# SC2.net
KiCad netlist of a schematic drawn in Altium Designer
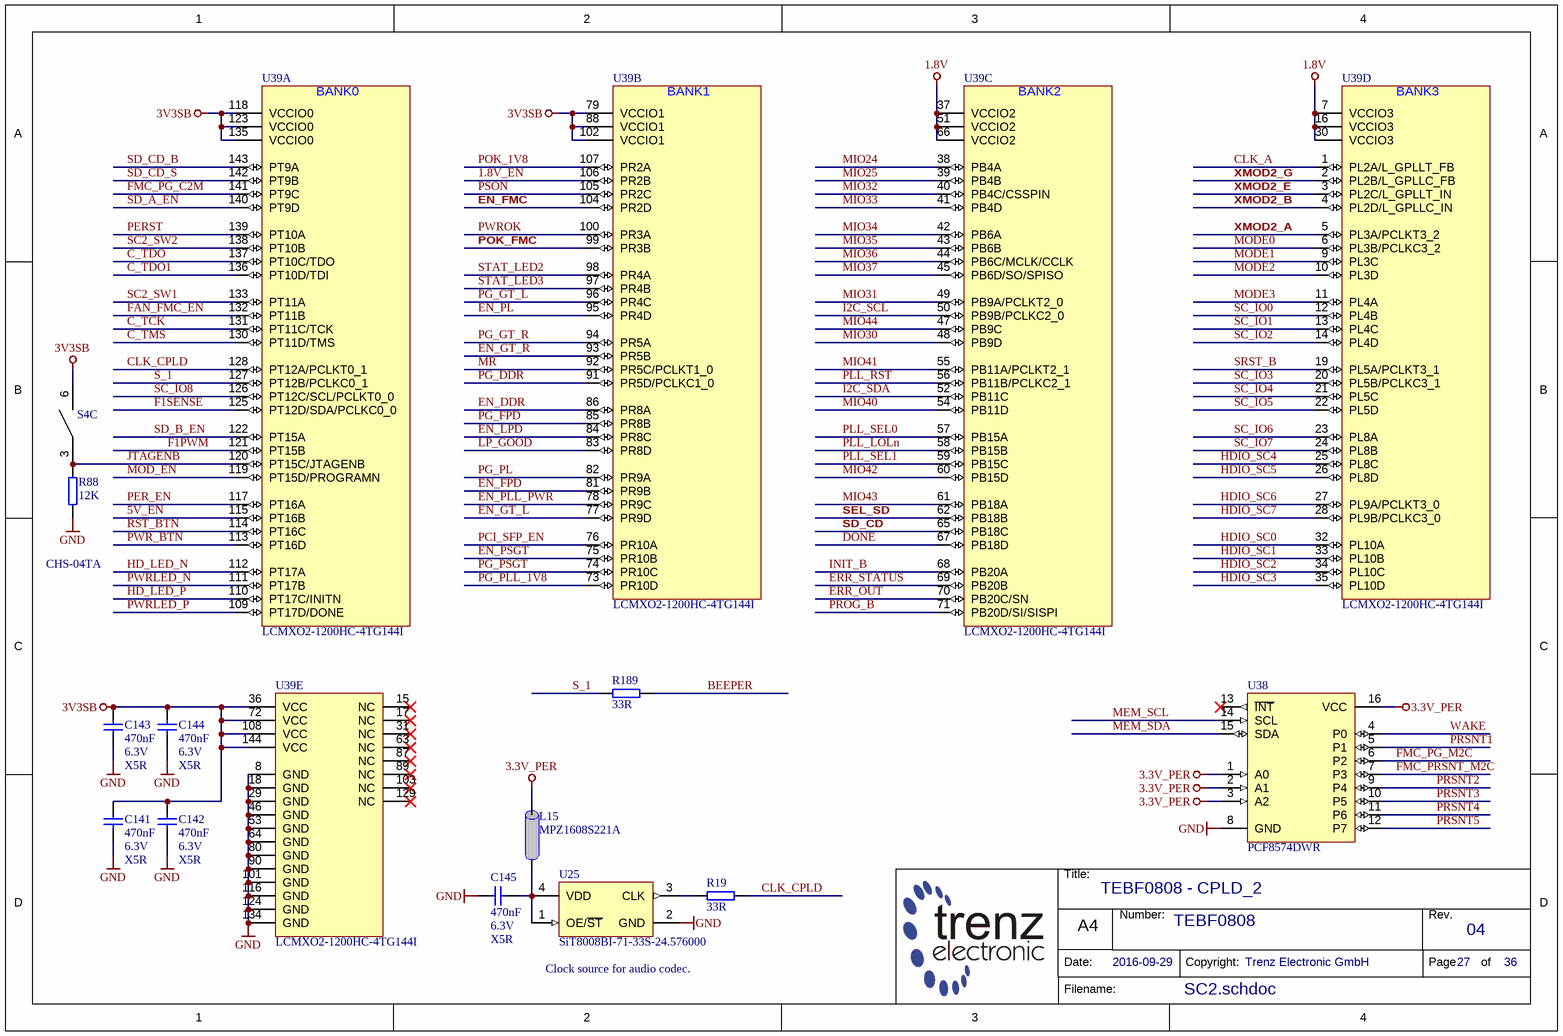
[diagram p0: SC2.schdoc]

(export (version "E")
  (design (tool "Eeschema 10.0.6"))
  (components
    (comp (ref "C141")
      (value "470nF")
      (footprint "CAPC1005X55N")
      (description "KON 470nF 6,3V X5R SMD")
      (fields (field (name "VOLTAGE") "6.3V") (field (name "TECHNOLOGY") "X5R"))
      (libsource (lib "TE") (part "CAP-NP"))
    )
    (comp (ref "C142")
      (value "470nF")
      (footprint "CAPC1005X55N")
      (description "KON 470nF 6,3V X5R SMD")
      (fields (field (name "VOLTAGE") "6.3V") (field (name "TECHNOLOGY") "X5R"))
      (libsource (lib "TE") (part "CAP-NP"))
    )
    (comp (ref "C143")
      (value "470nF")
      (footprint "CAPC1005X55N")
      (description "KON 470nF 6,3V X5R SMD")
      (fields (field (name "VOLTAGE") "6.3V") (field (name "TECHNOLOGY") "X5R"))
      (libsource (lib "TE") (part "CAP-NP"))
    )
    (comp (ref "C144")
      (value "470nF")
      (footprint "CAPC1005X55N")
      (description "KON 470nF 6,3V X5R SMD")
      (fields (field (name "VOLTAGE") "6.3V") (field (name "TECHNOLOGY") "X5R"))
      (libsource (lib "TE") (part "CAP-NP"))
    )
    (comp (ref "C145")
      (value "470nF")
      (footprint "CAPC1005X55N")
      (description "KON 470nF 6,3V X5R SMD")
      (fields (field (name "VOLTAGE") "6.3V") (field (name "TECHNOLOGY") "X5R"))
      (libsource (lib "TE") (part "CAP-NP"))
    )
    (comp (ref "L15")
      (value "MPZ1608S221A")
      (footprint "INDC1608X95N")
      (description "Ferritdurchführung MPZ1608S221A")
      (libsource (lib "TE") (part "Ferritperle"))
    )
    (comp (ref "R19")
      (value "33R")
      (footprint "RESC1005X40N")
      (description "WID SMD 33R 1% 0,063W")
      (fields (field (name "TOLERANCE") "1%"))
      (libsource (lib "TE") (part "RES"))
    )
    (comp (ref "R88")
      (value "12K")
      (footprint "RESC1005X40N")
      (description "WID SMD 12K 1% 0,063W")
      (fields (field (name "TOLERANCE") "1%"))
      (libsource (lib "TE") (part "RES"))
    )
    (comp (ref "R189")
      (value "33R")
      (footprint "RESC1005X40N")
      (description "WID SMD 33R 1% 0,063W")
      (fields (field (name "TOLERANCE") "1%"))
      (libsource (lib "TE") (part "RES"))
    )
    (comp (ref "S4")
      (value "CHS-04TA")
      (footprint "CHS-04TA")
      (description "DIP Schalter 4 fach 1,27mm SMD")
      (libsource (lib "TE") (part "CHS-04TA"))
    )
    (comp (ref "U25")
      (value "SiT8008BI-71-33S-24.576000")
      (footprint "2016")
      (description "SiT8008BI-71-33S-24.576000 MEMS Oszillator 24.576000MHz")
      (libsource (lib "TE") (part "SiT8103"))
    )
    (comp (ref "U38")
      (value "PCF8574DWR")
      (footprint "SOIC127P1030X265-16N")
      (libsource (lib "TE") (part "PCF8574DWR"))
    )
    (comp (ref "U39")
      (value "LCMXO2-1200HC-4TG144I")
      (footprint "QFP50P2200X2200X160-144N")
      (libsource (lib "TE") (part "LCMXO2-1200HC-4TG144"))
    )
  )
  (nets
    (net (code "1") (name "/1.8V_EN") (class "Default")
      (node (ref "U39") (pin "106") (pinfunction "PR2B_106") (pintype "bidirectional"))
    )
    (net (code "2") (name "/5V_EN") (class "Default")
      (node (ref "U39") (pin "115") (pinfunction "PT16B_115") (pintype "bidirectional"))
    )
    (net (code "3") (name "/BEEPER") (class "Default")
      (node (ref "R189") (pin "2") (pinfunction "2_2") (pintype "passive"))
    )
    (net (code "4") (name "/CLK_A") (class "Default")
      (node (ref "U39") (pin "1") (pinfunction "PL2A/L_GPLLT_FB_1") (pintype "bidirectional"))
    )
    (net (code "5") (name "/CLK_CPLD") (class "Default")
      (node (ref "R19") (pin "2") (pinfunction "2_2") (pintype "passive"))
      (node (ref "U39") (pin "128") (pinfunction "PT12A/PCLKT0_1_128") (pintype "bidirectional"))
    )
    (net (code "6") (name "/C_TCK") (class "Default")
      (node (ref "U39") (pin "131") (pinfunction "PT11C/TCK_131") (pintype "bidirectional"))
    )
    (net (code "7") (name "/C_TDO") (class "Default")
      (node (ref "U39") (pin "137") (pinfunction "PT10C/TDO_137") (pintype "bidirectional"))
    )
    (net (code "8") (name "/C_TDO1") (class "Default")
      (node (ref "U39") (pin "136") (pinfunction "PT10D/TDI_136") (pintype "bidirectional"))
    )
    (net (code "9") (name "/C_TMS") (class "Default")
      (node (ref "U39") (pin "130") (pinfunction "PT11D/TMS_130") (pintype "bidirectional"))
    )
    (net (code "10") (name "/DONE") (class "Default")
      (node (ref "U39") (pin "67") (pinfunction "PB18D_67") (pintype "bidirectional"))
    )
    (net (code "11") (name "/EN_DDR") (class "Default")
      (node (ref "U39") (pin "86") (pinfunction "PR8A_86") (pintype "bidirectional"))
    )
    (net (code "12") (name "/EN_FMC") (class "Default")
      (node (ref "U39") (pin "104") (pinfunction "PR2D_104") (pintype "bidirectional"))
    )
    (net (code "13") (name "/EN_FPD") (class "Default")
      (node (ref "U39") (pin "81") (pinfunction "PR9B_81") (pintype "bidirectional"))
    )
    (net (code "14") (name "/EN_GT_L") (class "Default")
      (node (ref "U39") (pin "77") (pinfunction "PR9D_77") (pintype "bidirectional"))
    )
    (net (code "15") (name "/EN_GT_R") (class "Default")
      (node (ref "U39") (pin "93") (pinfunction "PR5B_93") (pintype "bidirectional"))
    )
    (net (code "16") (name "/EN_LPD") (class "Default")
      (node (ref "U39") (pin "84") (pinfunction "PR8C_84") (pintype "bidirectional"))
    )
    (net (code "17") (name "/EN_PL") (class "Default")
      (node (ref "U39") (pin "95") (pinfunction "PR4D_95") (pintype "bidirectional"))
    )
    (net (code "18") (name "/EN_PLL_PWR") (class "Default")
      (node (ref "U39") (pin "78") (pinfunction "PR9C_78") (pintype "bidirectional"))
    )
    (net (code "19") (name "/EN_PSGT") (class "Default")
      (node (ref "U39") (pin "75") (pinfunction "PR10B_75") (pintype "bidirectional"))
    )
    (net (code "20") (name "/ERR_OUT") (class "Default")
      (node (ref "U39") (pin "70") (pinfunction "PB20C/SN_70") (pintype "bidirectional"))
    )
    (net (code "21") (name "/ERR_STATUS") (class "Default")
      (node (ref "U39") (pin "69") (pinfunction "PB20B_69") (pintype "bidirectional"))
    )
    (net (code "22") (name "/F1PWM") (class "Default")
      (node (ref "U39") (pin "121") (pinfunction "PT15B_121") (pintype "bidirectional"))
    )
    (net (code "23") (name "/F1SENSE") (class "Default")
      (node (ref "U39") (pin "125") (pinfunction "PT12D/SDA/PCLKC0_0_125") (pintype "bidirectional"))
    )
    (net (code "24") (name "/FAN_FMC_EN") (class "Default")
      (node (ref "U39") (pin "132") (pinfunction "PT11B_132") (pintype "bidirectional"))
    )
    (net (code "25") (name "/FMC_PG_C2M") (class "Default")
      (node (ref "U39") (pin "141") (pinfunction "PT9C_141") (pintype "bidirectional"))
    )
    (net (code "26") (name "/FMC_PG_M2C") (class "Default")
      (node (ref "U38") (pin "6") (pinfunction "P2_6") (pintype "bidirectional"))
    )
    (net (code "27") (name "/FMC_PRSNT_M2C") (class "Default")
      (node (ref "U38") (pin "7") (pinfunction "P3_7") (pintype "bidirectional"))
    )
    (net (code "28") (name "/HDIO_SC0") (class "Default")
      (node (ref "U39") (pin "32") (pinfunction "PL10A_32") (pintype "bidirectional"))
    )
    (net (code "29") (name "/HDIO_SC1") (class "Default")
      (node (ref "U39") (pin "33") (pinfunction "PL10B_33") (pintype "bidirectional"))
    )
    (net (code "30") (name "/HDIO_SC2") (class "Default")
      (node (ref "U39") (pin "34") (pinfunction "PL10C_34") (pintype "bidirectional"))
    )
    (net (code "31") (name "/HDIO_SC3") (class "Default")
      (node (ref "U39") (pin "35") (pinfunction "PL10D_35") (pintype "bidirectional"))
    )
    (net (code "32") (name "/HDIO_SC4") (class "Default")
      (node (ref "U39") (pin "25") (pinfunction "PL8C_25") (pintype "bidirectional"))
    )
    (net (code "33") (name "/HDIO_SC5") (class "Default")
      (node (ref "U39") (pin "26") (pinfunction "PL8D_26") (pintype "bidirectional"))
    )
    (net (code "34") (name "/HDIO_SC6") (class "Default")
      (node (ref "U39") (pin "27") (pinfunction "PL9A/PCLKT3_0_27") (pintype "bidirectional"))
    )
    (net (code "35") (name "/HDIO_SC7") (class "Default")
      (node (ref "U39") (pin "28") (pinfunction "PL9B/PCLKC3_0_28") (pintype "bidirectional"))
    )
    (net (code "36") (name "/HD_LED_N") (class "Default")
      (node (ref "U39") (pin "112") (pinfunction "PT17A_112") (pintype "bidirectional"))
    )
    (net (code "37") (name "/HD_LED_P") (class "Default")
      (node (ref "U39") (pin "110") (pinfunction "PT17C/INITN_110") (pintype "bidirectional"))
    )
    (net (code "38") (name "/I2C_SCL") (class "Default")
      (node (ref "U39") (pin "50") (pinfunction "PB9B/PCLKC2_0_50") (pintype "bidirectional"))
    )
    (net (code "39") (name "/I2C_SDA") (class "Default")
      (node (ref "U39") (pin "52") (pinfunction "PB11C_52") (pintype "bidirectional"))
    )
    (net (code "40") (name "/INIT_B") (class "Default")
      (node (ref "U39") (pin "68") (pinfunction "PB20A_68") (pintype "bidirectional"))
    )
    (net (code "41") (name "/JTAGENB") (class "Default")
      (node (ref "R88") (pin "2") (pinfunction "2_2") (pintype "passive"))
      (node (ref "S4") (pin "3") (pinfunction "3_3") (pintype "passive"))
      (node (ref "U39") (pin "120") (pinfunction "PT15C/JTAGENB_120") (pintype "bidirectional"))
    )
    (net (code "42") (name "/LP_GOOD") (class "Default")
      (node (ref "U39") (pin "83") (pinfunction "PR8D_83") (pintype "bidirectional"))
    )
    (net (code "43") (name "/MEM_SCL") (class "Default")
      (node (ref "U38") (pin "14") (pinfunction "SCL_14") (pintype "input"))
    )
    (net (code "44") (name "/MEM_SDA") (class "Default")
      (node (ref "U38") (pin "15") (pinfunction "SDA_15") (pintype "bidirectional"))
    )
    (net (code "45") (name "/MIO24") (class "Default")
      (node (ref "U39") (pin "38") (pinfunction "PB4A_38") (pintype "bidirectional"))
    )
    (net (code "46") (name "/MIO25") (class "Default")
      (node (ref "U39") (pin "39") (pinfunction "PB4B_39") (pintype "bidirectional"))
    )
    (net (code "47") (name "/MIO30") (class "Default")
      (node (ref "U39") (pin "48") (pinfunction "PB9D_48") (pintype "bidirectional"))
    )
    (net (code "48") (name "/MIO31") (class "Default")
      (node (ref "U39") (pin "49") (pinfunction "PB9A/PCLKT2_0_49") (pintype "bidirectional"))
    )
    (net (code "49") (name "/MIO32") (class "Default")
      (node (ref "U39") (pin "40") (pinfunction "PB4C/CSSPIN_40") (pintype "bidirectional"))
    )
    (net (code "50") (name "/MIO33") (class "Default")
      (node (ref "U39") (pin "41") (pinfunction "PB4D_41") (pintype "bidirectional"))
    )
    (net (code "51") (name "/MIO34") (class "Default")
      (node (ref "U39") (pin "42") (pinfunction "PB6A_42") (pintype "bidirectional"))
    )
    (net (code "52") (name "/MIO35") (class "Default")
      (node (ref "U39") (pin "43") (pinfunction "PB6B_43") (pintype "bidirectional"))
    )
    (net (code "53") (name "/MIO36") (class "Default")
      (node (ref "U39") (pin "44") (pinfunction "PB6C/MCLK/CCLK_44") (pintype "bidirectional"))
    )
    (net (code "54") (name "/MIO37") (class "Default")
      (node (ref "U39") (pin "45") (pinfunction "PB6D/SO/SPISO_45") (pintype "bidirectional"))
    )
    (net (code "55") (name "/MIO40") (class "Default")
      (node (ref "U39") (pin "54") (pinfunction "PB11D_54") (pintype "bidirectional"))
    )
    (net (code "56") (name "/MIO41") (class "Default")
      (node (ref "U39") (pin "55") (pinfunction "PB11A/PCLKT2_1_55") (pintype "bidirectional"))
    )
    (net (code "57") (name "/MIO42") (class "Default")
      (node (ref "U39") (pin "60") (pinfunction "PB15D_60") (pintype "bidirectional"))
    )
    (net (code "58") (name "/MIO43") (class "Default")
      (node (ref "U39") (pin "61") (pinfunction "PB18A_61") (pintype "bidirectional"))
    )
    (net (code "59") (name "/MIO44") (class "Default")
      (node (ref "U39") (pin "47") (pinfunction "PB9C_47") (pintype "bidirectional"))
    )
    (net (code "60") (name "/MODE0") (class "Default")
      (node (ref "U39") (pin "6") (pinfunction "PL3B/PCLKC3_2_6") (pintype "bidirectional"))
    )
    (net (code "61") (name "/MODE1") (class "Default")
      (node (ref "U39") (pin "9") (pinfunction "PL3C_9") (pintype "bidirectional"))
    )
    (net (code "62") (name "/MODE2") (class "Default")
      (node (ref "U39") (pin "10") (pinfunction "PL3D_10") (pintype "bidirectional"))
    )
    (net (code "63") (name "/MODE3") (class "Default")
      (node (ref "U39") (pin "11") (pinfunction "PL4A_11") (pintype "bidirectional"))
    )
    (net (code "64") (name "/MOD_EN") (class "Default")
      (node (ref "U39") (pin "119") (pinfunction "PT15D/PROGRAMN_119") (pintype "bidirectional"))
    )
    (net (code "65") (name "/MR") (class "Default")
      (node (ref "U39") (pin "92") (pinfunction "PR5C/PCLKT1_0_92") (pintype "bidirectional"))
    )
    (net (code "66") (name "/PCI_SFP_EN") (class "Default")
      (node (ref "U39") (pin "76") (pinfunction "PR10A_76") (pintype "bidirectional"))
    )
    (net (code "67") (name "/PERST") (class "Default")
      (node (ref "U39") (pin "139") (pinfunction "PT10A_139") (pintype "bidirectional"))
    )
    (net (code "68") (name "/PER_EN") (class "Default")
      (node (ref "U39") (pin "117") (pinfunction "PT16A_117") (pintype "bidirectional"))
    )
    (net (code "69") (name "/PG_DDR") (class "Default")
      (node (ref "U39") (pin "91") (pinfunction "PR5D/PCLKC1_0_91") (pintype "bidirectional"))
    )
    (net (code "70") (name "/PG_FPD") (class "Default")
      (node (ref "U39") (pin "85") (pinfunction "PR8B_85") (pintype "bidirectional"))
    )
    (net (code "71") (name "/PG_GT_L") (class "Default")
      (node (ref "U39") (pin "96") (pinfunction "PR4C_96") (pintype "bidirectional"))
    )
    (net (code "72") (name "/PG_GT_R") (class "Default")
      (node (ref "U39") (pin "94") (pinfunction "PR5A_94") (pintype "bidirectional"))
    )
    (net (code "73") (name "/PG_PL") (class "Default")
      (node (ref "U39") (pin "82") (pinfunction "PR9A_82") (pintype "bidirectional"))
    )
    (net (code "74") (name "/PG_PLL_1V8") (class "Default")
      (node (ref "U39") (pin "73") (pinfunction "PR10D_73") (pintype "bidirectional"))
    )
    (net (code "75") (name "/PG_PSGT") (class "Default")
      (node (ref "U39") (pin "74") (pinfunction "PR10C_74") (pintype "bidirectional"))
    )
    (net (code "76") (name "/PLL_LOLn") (class "Default")
      (node (ref "U39") (pin "58") (pinfunction "PB15B_58") (pintype "bidirectional"))
    )
    (net (code "77") (name "/PLL_RST") (class "Default")
      (node (ref "U39") (pin "56") (pinfunction "PB11B/PCLKC2_1_56") (pintype "bidirectional"))
    )
    (net (code "78") (name "/PLL_SEL0") (class "Default")
      (node (ref "U39") (pin "57") (pinfunction "PB15A_57") (pintype "bidirectional"))
    )
    (net (code "79") (name "/PLL_SEL1") (class "Default")
      (node (ref "U39") (pin "59") (pinfunction "PB15C_59") (pintype "bidirectional"))
    )
    (net (code "80") (name "/POK_1V8") (class "Default")
      (node (ref "U39") (pin "107") (pinfunction "PR2A_107") (pintype "bidirectional"))
    )
    (net (code "81") (name "/POK_FMC") (class "Default")
      (node (ref "U39") (pin "99") (pinfunction "PR3B_99") (pintype "bidirectional"))
    )
    (net (code "82") (name "/PROG_B") (class "Default")
      (node (ref "U39") (pin "71") (pinfunction "PB20D/SI/SISPI_71") (pintype "bidirectional"))
    )
    (net (code "83") (name "/PRSNT1") (class "Default")
      (node (ref "U38") (pin "5") (pinfunction "P1_5") (pintype "bidirectional"))
    )
    (net (code "84") (name "/PRSNT2") (class "Default")
      (node (ref "U38") (pin "9") (pinfunction "P4_9") (pintype "bidirectional"))
    )
    (net (code "85") (name "/PRSNT3") (class "Default")
      (node (ref "U38") (pin "10") (pinfunction "P5_10") (pintype "bidirectional"))
    )
    (net (code "86") (name "/PRSNT4") (class "Default")
      (node (ref "U38") (pin "11") (pinfunction "P6_11") (pintype "bidirectional"))
    )
    (net (code "87") (name "/PRSNT5") (class "Default")
      (node (ref "U38") (pin "12") (pinfunction "P7_12") (pintype "bidirectional"))
    )
    (net (code "88") (name "/PSON") (class "Default")
      (node (ref "U39") (pin "105") (pinfunction "PR2C_105") (pintype "bidirectional"))
    )
    (net (code "89") (name "/PWRLED_N") (class "Default")
      (node (ref "U39") (pin "111") (pinfunction "PT17B_111") (pintype "bidirectional"))
    )
    (net (code "90") (name "/PWRLED_P") (class "Default")
      (node (ref "U39") (pin "109") (pinfunction "PT17D/DONE_109") (pintype "bidirectional"))
    )
    (net (code "91") (name "/PWROK") (class "Default")
      (node (ref "U39") (pin "100") (pinfunction "PR3A_100") (pintype "bidirectional"))
    )
    (net (code "92") (name "/PWR_BTN") (class "Default")
      (node (ref "U39") (pin "113") (pinfunction "PT16D_113") (pintype "bidirectional"))
    )
    (net (code "93") (name "/RST_BTN") (class "Default")
      (node (ref "U39") (pin "114") (pinfunction "PT16C_114") (pintype "bidirectional"))
    )
    (net (code "94") (name "/SC2_SW1") (class "Default")
      (node (ref "U39") (pin "133") (pinfunction "PT11A_133") (pintype "bidirectional"))
    )
    (net (code "95") (name "/SC2_SW2") (class "Default")
      (node (ref "U39") (pin "138") (pinfunction "PT10B_138") (pintype "bidirectional"))
    )
    (net (code "96") (name "/SC_IO0") (class "Default")
      (node (ref "U39") (pin "12") (pinfunction "PL4B_12") (pintype "bidirectional"))
    )
    (net (code "97") (name "/SC_IO1") (class "Default")
      (node (ref "U39") (pin "13") (pinfunction "PL4C_13") (pintype "bidirectional"))
    )
    (net (code "98") (name "/SC_IO2") (class "Default")
      (node (ref "U39") (pin "14") (pinfunction "PL4D_14") (pintype "bidirectional"))
    )
    (net (code "99") (name "/SC_IO3") (class "Default")
      (node (ref "U39") (pin "20") (pinfunction "PL5B/PCLKC3_1_20") (pintype "bidirectional"))
    )
    (net (code "100") (name "/SC_IO4") (class "Default")
      (node (ref "U39") (pin "21") (pinfunction "PL5C_21") (pintype "bidirectional"))
    )
    (net (code "101") (name "/SC_IO5") (class "Default")
      (node (ref "U39") (pin "22") (pinfunction "PL5D_22") (pintype "bidirectional"))
    )
    (net (code "102") (name "/SC_IO6") (class "Default")
      (node (ref "U39") (pin "23") (pinfunction "PL8A_23") (pintype "bidirectional"))
    )
    (net (code "103") (name "/SC_IO7") (class "Default")
      (node (ref "U39") (pin "24") (pinfunction "PL8B_24") (pintype "bidirectional"))
    )
    (net (code "104") (name "/SC_IO8") (class "Default")
      (node (ref "U39") (pin "126") (pinfunction "PT12C/SCL/PCLKT0_0_126") (pintype "bidirectional"))
    )
    (net (code "105") (name "/SD_A_EN") (class "Default")
      (node (ref "U39") (pin "140") (pinfunction "PT9D_140") (pintype "bidirectional"))
    )
    (net (code "106") (name "/SD_B_EN") (class "Default")
      (node (ref "U39") (pin "122") (pinfunction "PT15A_122") (pintype "bidirectional"))
    )
    (net (code "107") (name "/SD_CD") (class "Default")
      (node (ref "U39") (pin "65") (pinfunction "PB18C_65") (pintype "bidirectional"))
    )
    (net (code "108") (name "/SD_CD_B") (class "Default")
      (node (ref "U39") (pin "143") (pinfunction "PT9A_143") (pintype "bidirectional"))
    )
    (net (code "109") (name "/SD_CD_S") (class "Default")
      (node (ref "U39") (pin "142") (pinfunction "PT9B_142") (pintype "bidirectional"))
    )
    (net (code "110") (name "/SEL_SD") (class "Default")
      (node (ref "U39") (pin "62") (pinfunction "PB18B_62") (pintype "bidirectional"))
    )
    (net (code "111") (name "/SRST_B") (class "Default")
      (node (ref "U39") (pin "19") (pinfunction "PL5A/PCLKT3_1_19") (pintype "bidirectional"))
    )
    (net (code "112") (name "/STAT_LED2") (class "Default")
      (node (ref "U39") (pin "98") (pinfunction "PR4A_98") (pintype "bidirectional"))
    )
    (net (code "113") (name "/STAT_LED3") (class "Default")
      (node (ref "U39") (pin "97") (pinfunction "PR4B_97") (pintype "bidirectional"))
    )
    (net (code "114") (name "/S_1") (class "Default")
      (node (ref "R189") (pin "1") (pinfunction "1_1") (pintype "passive"))
      (node (ref "U39") (pin "127") (pinfunction "PT12B/PCLKC0_1_127") (pintype "bidirectional"))
    )
    (net (code "115") (name "/WAKE") (class "Default")
      (node (ref "U38") (pin "4") (pinfunction "P0_4") (pintype "bidirectional"))
    )
    (net (code "116") (name "/XMOD2_A") (class "Default")
      (node (ref "U39") (pin "5") (pinfunction "PL3A/PCLKT3_2_5") (pintype "bidirectional"))
    )
    (net (code "117") (name "/XMOD2_B") (class "Default")
      (node (ref "U39") (pin "4") (pinfunction "PL2D/L_GPLLC_IN_4") (pintype "bidirectional"))
    )
    (net (code "118") (name "/XMOD2_E") (class "Default")
      (node (ref "U39") (pin "3") (pinfunction "PL2C/L_GPLLT_IN_3") (pintype "bidirectional"))
    )
    (net (code "119") (name "/XMOD2_G") (class "Default")
      (node (ref "U39") (pin "2") (pinfunction "PL2B/L_GPLLC_FB_2") (pintype "bidirectional"))
    )
    (net (code "120") (name "1.8V") (class "Default")
      (node (ref "U39") (pin "16") (pinfunction "VCCIO3_16") (pintype "power_in"))
      (node (ref "U39") (pin "30") (pinfunction "VCCIO3_30") (pintype "power_in"))
      (node (ref "U39") (pin "37") (pinfunction "VCCIO2_37") (pintype "power_in"))
      (node (ref "U39") (pin "51") (pinfunction "VCCIO2_51") (pintype "power_in"))
      (node (ref "U39") (pin "66") (pinfunction "VCCIO2_66") (pintype "power_in"))
      (node (ref "U39") (pin "7") (pinfunction "VCCIO3_7") (pintype "power_in"))
    )
    (net (code "121") (name "3.3V_PER") (class "Default")
      (node (ref "L15") (pin "2") (pinfunction "2_2") (pintype "passive"))
      (node (ref "U38") (pin "1") (pinfunction "A0_1") (pintype "input"))
      (node (ref "U38") (pin "16") (pinfunction "VCC_16") (pintype "power_in"))
      (node (ref "U38") (pin "2") (pinfunction "A1_2") (pintype "input"))
      (node (ref "U38") (pin "3") (pinfunction "A2_3") (pintype "input"))
    )
    (net (code "122") (name "3V3SB") (class "Default")
      (node (ref "C141") (pin "1") (pinfunction "1_1") (pintype "passive"))
      (node (ref "C142") (pin "1") (pinfunction "1_1") (pintype "passive"))
      (node (ref "C143") (pin "1") (pinfunction "1_1") (pintype "passive"))
      (node (ref "C144") (pin "1") (pinfunction "1_1") (pintype "passive"))
      (node (ref "S4") (pin "6") (pinfunction "6_6") (pintype "passive"))
      (node (ref "U39") (pin "102") (pinfunction "VCCIO1_102") (pintype "power_in"))
      (node (ref "U39") (pin "108") (pinfunction "VCC_108") (pintype "power_in"))
      (node (ref "U39") (pin "118") (pinfunction "VCCIO0_118") (pintype "power_in"))
      (node (ref "U39") (pin "123") (pinfunction "VCCIO0_123") (pintype "power_in"))
      (node (ref "U39") (pin "135") (pinfunction "VCCIO0_135") (pintype "power_in"))
      (node (ref "U39") (pin "144") (pinfunction "VCC_144") (pintype "power_in"))
      (node (ref "U39") (pin "36") (pinfunction "VCC_36") (pintype "power_in"))
      (node (ref "U39") (pin "72") (pinfunction "VCC_72") (pintype "power_in"))
      (node (ref "U39") (pin "79") (pinfunction "VCCIO1_79") (pintype "power_in"))
      (node (ref "U39") (pin "88") (pinfunction "VCCIO1_88") (pintype "power_in"))
    )
    (net (code "123") (name "GND") (class "Default")
      (node (ref "C141") (pin "2") (pinfunction "2_2") (pintype "passive"))
      (node (ref "C142") (pin "2") (pinfunction "2_2") (pintype "passive"))
      (node (ref "C143") (pin "2") (pinfunction "2_2") (pintype "passive"))
      (node (ref "C144") (pin "2") (pinfunction "2_2") (pintype "passive"))
      (node (ref "C145") (pin "2") (pinfunction "2_2") (pintype "passive"))
      (node (ref "R88") (pin "1") (pinfunction "1_1") (pintype "passive"))
      (node (ref "U25") (pin "2") (pinfunction "GND_2") (pintype "power_in"))
      (node (ref "U38") (pin "8") (pinfunction "GND_8") (pintype "power_in"))
      (node (ref "U39") (pin "101") (pinfunction "GND_101") (pintype "power_in"))
      (node (ref "U39") (pin "116") (pinfunction "GND_116") (pintype "power_in"))
      (node (ref "U39") (pin "124") (pinfunction "GND_124") (pintype "power_in"))
      (node (ref "U39") (pin "134") (pinfunction "GND_134") (pintype "power_in"))
      (node (ref "U39") (pin "18") (pinfunction "GND_18") (pintype "power_in"))
      (node (ref "U39") (pin "29") (pinfunction "GND_29") (pintype "power_in"))
      (node (ref "U39") (pin "46") (pinfunction "GND_46") (pintype "power_in"))
      (node (ref "U39") (pin "53") (pinfunction "GND_53") (pintype "power_in"))
      (node (ref "U39") (pin "64") (pinfunction "GND_64") (pintype "power_in"))
      (node (ref "U39") (pin "8") (pinfunction "GND_8") (pintype "power_in"))
      (node (ref "U39") (pin "80") (pinfunction "GND_80") (pintype "power_in"))
      (node (ref "U39") (pin "90") (pinfunction "GND_90") (pintype "power_in"))
    )
    (net (code "124") (name "Net-(U25-CLK)") (class "Default")
      (node (ref "R19") (pin "1") (pinfunction "1_1") (pintype "passive"))
      (node (ref "U25") (pin "3") (pinfunction "CLK_3") (pintype "output"))
    )
    (net (code "125") (name "Net-(U25-OE{slash}~{ST})") (class "Default")
      (node (ref "C145") (pin "1") (pinfunction "1_1") (pintype "passive"))
      (node (ref "L15") (pin "1") (pinfunction "1_1") (pintype "passive"))
      (node (ref "U25") (pin "1") (pinfunction "OE/~{ST}_1") (pintype "input"))
      (node (ref "U25") (pin "4") (pinfunction "VDD_4") (pintype "power_in"))
    )
    (net (code "126") (name "unconnected-(U38-~{INT}-Pad13)") (class "Default")
      (node (ref "U38") (pin "13") (pinfunction "~{INT}_13") (pintype "output+no_connect"))
    )
    (net (code "127") (name "unconnected-(U39E-NC-Pad15)") (class "Default")
      (node (ref "U39") (pin "15") (pinfunction "NC_15") (pintype "passive+no_connect"))
    )
    (net (code "128") (name "unconnected-(U39E-NC-Pad17)") (class "Default")
      (node (ref "U39") (pin "17") (pinfunction "NC_17") (pintype "passive+no_connect"))
    )
    (net (code "129") (name "unconnected-(U39E-NC-Pad31)") (class "Default")
      (node (ref "U39") (pin "31") (pinfunction "NC_31") (pintype "passive+no_connect"))
    )
    (net (code "130") (name "unconnected-(U39E-NC-Pad63)") (class "Default")
      (node (ref "U39") (pin "63") (pinfunction "NC_63") (pintype "passive+no_connect"))
    )
    (net (code "131") (name "unconnected-(U39E-NC-Pad87)") (class "Default")
      (node (ref "U39") (pin "87") (pinfunction "NC_87") (pintype "passive+no_connect"))
    )
    (net (code "132") (name "unconnected-(U39E-NC-Pad89)") (class "Default")
      (node (ref "U39") (pin "89") (pinfunction "NC_89") (pintype "passive+no_connect"))
    )
    (net (code "133") (name "unconnected-(U39E-NC-Pad103)") (class "Default")
      (node (ref "U39") (pin "103") (pinfunction "NC_103") (pintype "passive+no_connect"))
    )
    (net (code "134") (name "unconnected-(U39E-NC-Pad129)") (class "Default")
      (node (ref "U39") (pin "129") (pinfunction "NC_129") (pintype "passive+no_connect"))
    )
  )
)
